# REFCLK.net
KiCad netlist of a schematic drawn in Altium Designer
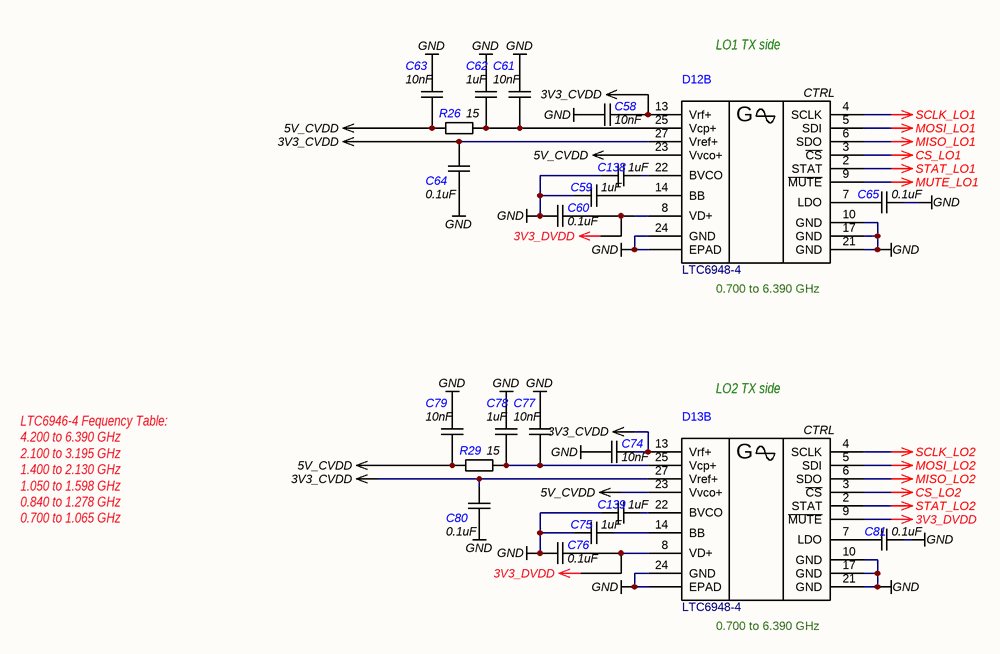
[diagram p0: REFCLK.SchDoc]

(export (version "E")
  (design (tool "Eeschema 10.0.6"))
  (components
    (comp (ref "C58")
      (value "10nF")
      (footprint "C0402")
      (description "SMD Capacitor")
      (fields (field (name "MANUFACTURER") "Murata") (field (name "TOLERANCE") "10%"))
      (libsource (lib "Kintex_SDR") (part "CAP"))
    )
    (comp (ref "C59")
      (value "1uF")
      (footprint "C0402")
      (description "SMD Capacitor")
      (fields (field (name "MANUFACTURER") "Murata") (field (name "TOLERANCE") "10%"))
      (libsource (lib "Kintex_SDR") (part "CAP"))
    )
    (comp (ref "C60")
      (value "0.1uF")
      (footprint "C0402")
      (description "SMD Capacitor")
      (fields (field (name "MANUFACTURER") "Murata") (field (name "TOLERANCE") "10%"))
      (libsource (lib "Kintex_SDR") (part "CAP"))
    )
    (comp (ref "C61")
      (value "10nF")
      (footprint "C0402")
      (description "SMD Capacitor")
      (fields (field (name "MANUFACTURER") "Murata") (field (name "TOLERANCE") "10%"))
      (libsource (lib "Kintex_SDR") (part "CAP"))
    )
    (comp (ref "C62")
      (value "1uF")
      (footprint "C0402")
      (description "SMD Capacitor")
      (fields (field (name "MANUFACTURER") "Murata") (field (name "TOLERANCE") "10%"))
      (libsource (lib "Kintex_SDR") (part "CAP"))
    )
    (comp (ref "C63")
      (value "10nF")
      (footprint "C0402")
      (description "SMD Capacitor")
      (fields (field (name "MANUFACTURER") "Murata") (field (name "TOLERANCE") "10%"))
      (libsource (lib "Kintex_SDR") (part "CAP"))
    )
    (comp (ref "C64")
      (value "0.1uF")
      (footprint "C0402")
      (description "SMD Capacitor")
      (fields (field (name "MANUFACTURER") "Murata") (field (name "TOLERANCE") "10%"))
      (libsource (lib "Kintex_SDR") (part "CAP"))
    )
    (comp (ref "C65")
      (value "0.1uF")
      (footprint "C0402")
      (description "SMD Capacitor")
      (fields (field (name "MANUFACTURER") "Murata") (field (name "TOLERANCE") "10%"))
      (libsource (lib "Kintex_SDR") (part "CAP"))
    )
    (comp (ref "C74")
      (value "10nF")
      (footprint "C0402")
      (description "SMD Capacitor")
      (fields (field (name "MANUFACTURER") "Murata") (field (name "TOLERANCE") "10%"))
      (libsource (lib "Kintex_SDR") (part "CAP"))
    )
    (comp (ref "C75")
      (value "1uF")
      (footprint "C0402")
      (description "SMD Capacitor")
      (fields (field (name "MANUFACTURER") "Murata") (field (name "TOLERANCE") "10%"))
      (libsource (lib "Kintex_SDR") (part "CAP"))
    )
    (comp (ref "C76")
      (value "0.1uF")
      (footprint "C0402")
      (description "SMD Capacitor")
      (fields (field (name "MANUFACTURER") "Murata") (field (name "TOLERANCE") "10%"))
      (libsource (lib "Kintex_SDR") (part "CAP"))
    )
    (comp (ref "C77")
      (value "10nF")
      (footprint "C0402")
      (description "SMD Capacitor")
      (fields (field (name "MANUFACTURER") "Murata") (field (name "TOLERANCE") "10%"))
      (libsource (lib "Kintex_SDR") (part "CAP"))
    )
    (comp (ref "C78")
      (value "1uF")
      (footprint "C0402")
      (description "SMD Capacitor")
      (fields (field (name "MANUFACTURER") "Murata") (field (name "TOLERANCE") "10%"))
      (libsource (lib "Kintex_SDR") (part "CAP"))
    )
    (comp (ref "C79")
      (value "10nF")
      (footprint "C0402")
      (description "SMD Capacitor")
      (fields (field (name "MANUFACTURER") "Murata") (field (name "TOLERANCE") "10%"))
      (libsource (lib "Kintex_SDR") (part "CAP"))
    )
    (comp (ref "C80")
      (value "0.1uF")
      (footprint "C0402")
      (description "SMD Capacitor")
      (fields (field (name "MANUFACTURER") "Murata") (field (name "TOLERANCE") "10%"))
      (libsource (lib "Kintex_SDR") (part "CAP"))
    )
    (comp (ref "C81")
      (value "0.1uF")
      (footprint "C0402")
      (description "SMD Capacitor")
      (fields (field (name "MANUFACTURER") "Murata") (field (name "TOLERANCE") "10%"))
      (libsource (lib "Kintex_SDR") (part "CAP"))
    )
    (comp (ref "C138")
      (value "1uF")
      (footprint "C0402")
      (description "SMD Capacitor")
      (fields (field (name "MANUFACTURER") "Murata") (field (name "TOLERANCE") "10%"))
      (libsource (lib "Kintex_SDR") (part "CAP"))
    )
    (comp (ref "C139")
      (value "1uF")
      (footprint "C0402")
      (description "SMD Capacitor")
      (fields (field (name "MANUFACTURER") "Murata") (field (name "TOLERANCE") "10%"))
      (libsource (lib "Kintex_SDR") (part "CAP"))
    )
    (comp (ref "D12")
      (value "LTC6948-4")
      (footprint "QFN-28")
      (description "The LTC®LTC6948 is a high performance, low noise, 6.39GHz  phase-locked loop (PLL)")
      (fields
        (field (name "MANUFACTURER") "Linear Technology")
        (field (name "VOLTAGE") "3.15 V ~ 5.25 V")
        (field (name "FREQUENCY RANGE") "0.700 to 6.390 GHz")
      )
      (libsource (lib "DBLib") (part "LTC6948"))
    )
    (comp (ref "D13")
      (value "LTC6948-4")
      (footprint "QFN-28")
      (description "The LTC®LTC6948 is a high performance, low noise, 6.39GHz  phase-locked loop (PLL)")
      (fields
        (field (name "MANUFACTURER") "Linear Technology")
        (field (name "VOLTAGE") "3.15 V ~ 5.25 V")
        (field (name "FREQUENCY RANGE") "0.700 to 6.390 GHz")
      )
      (libsource (lib "DBLib") (part "LTC6948"))
    )
    (comp (ref "R26")
      (value "15")
      (footprint "R0603")
      (description "SMD Resistor")
      (fields (field (name "POWER") "0.1 Wt") (field (name "TOLERANCE") "1%"))
      (libsource (lib "Kintex_SDR") (part "RES"))
    )
    (comp (ref "R29")
      (value "15")
      (footprint "R0603")
      (description "SMD Resistor")
      (fields (field (name "POWER") "0.1 Wt") (field (name "TOLERANCE") "1%"))
      (libsource (lib "Kintex_SDR") (part "RES"))
    )
  )
  (nets
    (net (code "1") (name "3V3_CVDD") (class "Default")
      (node (ref "C58") (pin "1") (pinfunction "1_1") (pintype "passive"))
      (node (ref "C64") (pin "2") (pinfunction "2_2") (pintype "passive"))
      (node (ref "C74") (pin "1") (pinfunction "1_1") (pintype "passive"))
      (node (ref "C80") (pin "2") (pinfunction "2_2") (pintype "passive"))
      (node (ref "D12") (pin "13") (pinfunction "Vrf+_13") (pintype "passive"))
      (node (ref "D12") (pin "27") (pinfunction "Vref+_27") (pintype "passive"))
      (node (ref "D13") (pin "13") (pinfunction "Vrf+_13") (pintype "passive"))
      (node (ref "D13") (pin "27") (pinfunction "Vref+_27") (pintype "passive"))
    )
    (net (code "2") (name "3V3_DVDD") (class "Default")
      (node (ref "C60") (pin "2") (pinfunction "2_2") (pintype "passive"))
      (node (ref "C76") (pin "2") (pinfunction "2_2") (pintype "passive"))
      (node (ref "D12") (pin "8") (pinfunction "VD+_8") (pintype "passive"))
      (node (ref "D13") (pin "8") (pinfunction "VD+_8") (pintype "passive"))
      (node (ref "D13") (pin "9") (pinfunction "~{MUTE}_9") (pintype "passive"))
    )
    (net (code "3") (name "5V_CVDD") (class "Default")
      (node (ref "C63") (pin "2") (pinfunction "2_2") (pintype "passive"))
      (node (ref "C79") (pin "2") (pinfunction "2_2") (pintype "passive"))
      (node (ref "D12") (pin "23") (pinfunction "Vvco+_23") (pintype "passive"))
      (node (ref "D13") (pin "23") (pinfunction "Vvco+_23") (pintype "passive"))
      (node (ref "R26") (pin "2") (pinfunction "2_2") (pintype "passive"))
      (node (ref "R29") (pin "2") (pinfunction "2_2") (pintype "passive"))
    )
    (net (code "4") (name "CS_LO1") (class "Default")
      (node (ref "D12") (pin "3") (pinfunction "~{CS}_3") (pintype "passive"))
    )
    (net (code "5") (name "CS_LO2") (class "Default")
      (node (ref "D13") (pin "3") (pinfunction "~{CS}_3") (pintype "passive"))
    )
    (net (code "6") (name "GND") (class "Default")
      (node (ref "C138") (pin "1") (pinfunction "1_1") (pintype "passive"))
      (node (ref "C139") (pin "1") (pinfunction "1_1") (pintype "passive"))
      (node (ref "C58") (pin "2") (pinfunction "2_2") (pintype "passive"))
      (node (ref "C59") (pin "1") (pinfunction "1_1") (pintype "passive"))
      (node (ref "C60") (pin "1") (pinfunction "1_1") (pintype "passive"))
      (node (ref "C61") (pin "1") (pinfunction "1_1") (pintype "passive"))
      (node (ref "C62") (pin "1") (pinfunction "1_1") (pintype "passive"))
      (node (ref "C63") (pin "1") (pinfunction "1_1") (pintype "passive"))
      (node (ref "C64") (pin "1") (pinfunction "1_1") (pintype "passive"))
      (node (ref "C65") (pin "1") (pinfunction "1_1") (pintype "passive"))
      (node (ref "C74") (pin "2") (pinfunction "2_2") (pintype "passive"))
      (node (ref "C75") (pin "1") (pinfunction "1_1") (pintype "passive"))
      (node (ref "C76") (pin "1") (pinfunction "1_1") (pintype "passive"))
      (node (ref "C77") (pin "1") (pinfunction "1_1") (pintype "passive"))
      (node (ref "C78") (pin "1") (pinfunction "1_1") (pintype "passive"))
      (node (ref "C79") (pin "1") (pinfunction "1_1") (pintype "passive"))
      (node (ref "C80") (pin "1") (pinfunction "1_1") (pintype "passive"))
      (node (ref "C81") (pin "1") (pinfunction "1_1") (pintype "passive"))
      (node (ref "D12") (pin "10") (pinfunction "GND_10") (pintype "passive"))
      (node (ref "D12") (pin "17") (pinfunction "GND_17") (pintype "passive"))
      (node (ref "D12") (pin "21") (pinfunction "GND_21") (pintype "passive"))
      (node (ref "D12") (pin "24") (pinfunction "GND_24") (pintype "passive"))
      (node (ref "D12") (pin "29") (pinfunction "EPAD_29") (pintype "passive"))
      (node (ref "D13") (pin "10") (pinfunction "GND_10") (pintype "passive"))
      (node (ref "D13") (pin "17") (pinfunction "GND_17") (pintype "passive"))
      (node (ref "D13") (pin "21") (pinfunction "GND_21") (pintype "passive"))
      (node (ref "D13") (pin "24") (pinfunction "GND_24") (pintype "passive"))
      (node (ref "D13") (pin "29") (pinfunction "EPAD_29") (pintype "passive"))
    )
    (net (code "7") (name "MISO_LO1") (class "Default")
      (node (ref "D12") (pin "6") (pinfunction "SDO_6") (pintype "passive"))
    )
    (net (code "8") (name "MISO_LO2") (class "Default")
      (node (ref "D13") (pin "6") (pinfunction "SDO_6") (pintype "passive"))
    )
    (net (code "9") (name "MOSI_LO1") (class "Default")
      (node (ref "D12") (pin "5") (pinfunction "SDI_5") (pintype "passive"))
    )
    (net (code "10") (name "MOSI_LO2") (class "Default")
      (node (ref "D13") (pin "5") (pinfunction "SDI_5") (pintype "passive"))
    )
    (net (code "11") (name "MUTE_LO1") (class "Default")
      (node (ref "D12") (pin "9") (pinfunction "~{MUTE}_9") (pintype "passive"))
    )
    (net (code "12") (name "Net-(D12B-BB)") (class "Default")
      (node (ref "C59") (pin "2") (pinfunction "2_2") (pintype "passive"))
      (node (ref "D12") (pin "14") (pinfunction "BB_14") (pintype "passive"))
    )
    (net (code "13") (name "Net-(D12B-BVCO)") (class "Default")
      (node (ref "C138") (pin "2") (pinfunction "2_2") (pintype "passive"))
      (node (ref "D12") (pin "22") (pinfunction "BVCO_22") (pintype "passive"))
    )
    (net (code "14") (name "Net-(D12B-LDO)") (class "Default")
      (node (ref "C65") (pin "2") (pinfunction "2_2") (pintype "passive"))
      (node (ref "D12") (pin "7") (pinfunction "LDO_7") (pintype "passive"))
    )
    (net (code "15") (name "Net-(D12B-Vcp+)") (class "Default")
      (node (ref "C61") (pin "2") (pinfunction "2_2") (pintype "passive"))
      (node (ref "C62") (pin "2") (pinfunction "2_2") (pintype "passive"))
      (node (ref "D12") (pin "25") (pinfunction "Vcp+_25") (pintype "passive"))
      (node (ref "R26") (pin "1") (pinfunction "1_1") (pintype "passive"))
    )
    (net (code "16") (name "Net-(D13B-BB)") (class "Default")
      (node (ref "C75") (pin "2") (pinfunction "2_2") (pintype "passive"))
      (node (ref "D13") (pin "14") (pinfunction "BB_14") (pintype "passive"))
    )
    (net (code "17") (name "Net-(D13B-BVCO)") (class "Default")
      (node (ref "C139") (pin "2") (pinfunction "2_2") (pintype "passive"))
      (node (ref "D13") (pin "22") (pinfunction "BVCO_22") (pintype "passive"))
    )
    (net (code "18") (name "Net-(D13B-LDO)") (class "Default")
      (node (ref "C81") (pin "2") (pinfunction "2_2") (pintype "passive"))
      (node (ref "D13") (pin "7") (pinfunction "LDO_7") (pintype "passive"))
    )
    (net (code "19") (name "Net-(D13B-Vcp+)") (class "Default")
      (node (ref "C77") (pin "2") (pinfunction "2_2") (pintype "passive"))
      (node (ref "C78") (pin "2") (pinfunction "2_2") (pintype "passive"))
      (node (ref "D13") (pin "25") (pinfunction "Vcp+_25") (pintype "passive"))
      (node (ref "R29") (pin "1") (pinfunction "1_1") (pintype "passive"))
    )
    (net (code "20") (name "SCLK_LO1") (class "Default")
      (node (ref "D12") (pin "4") (pinfunction "SCLK_4") (pintype "passive"))
    )
    (net (code "21") (name "SCLK_LO2") (class "Default")
      (node (ref "D13") (pin "4") (pinfunction "SCLK_4") (pintype "passive"))
    )
    (net (code "22") (name "STAT_LO1") (class "Default")
      (node (ref "D12") (pin "2") (pinfunction "STAT_2") (pintype "passive"))
    )
    (net (code "23") (name "STAT_LO2") (class "Default")
      (node (ref "D13") (pin "2") (pinfunction "STAT_2") (pintype "passive"))
    )
  )
)
